# usb2cmi_mini_disp.net
KiCad netlist of a schematic drawn in EAGLE
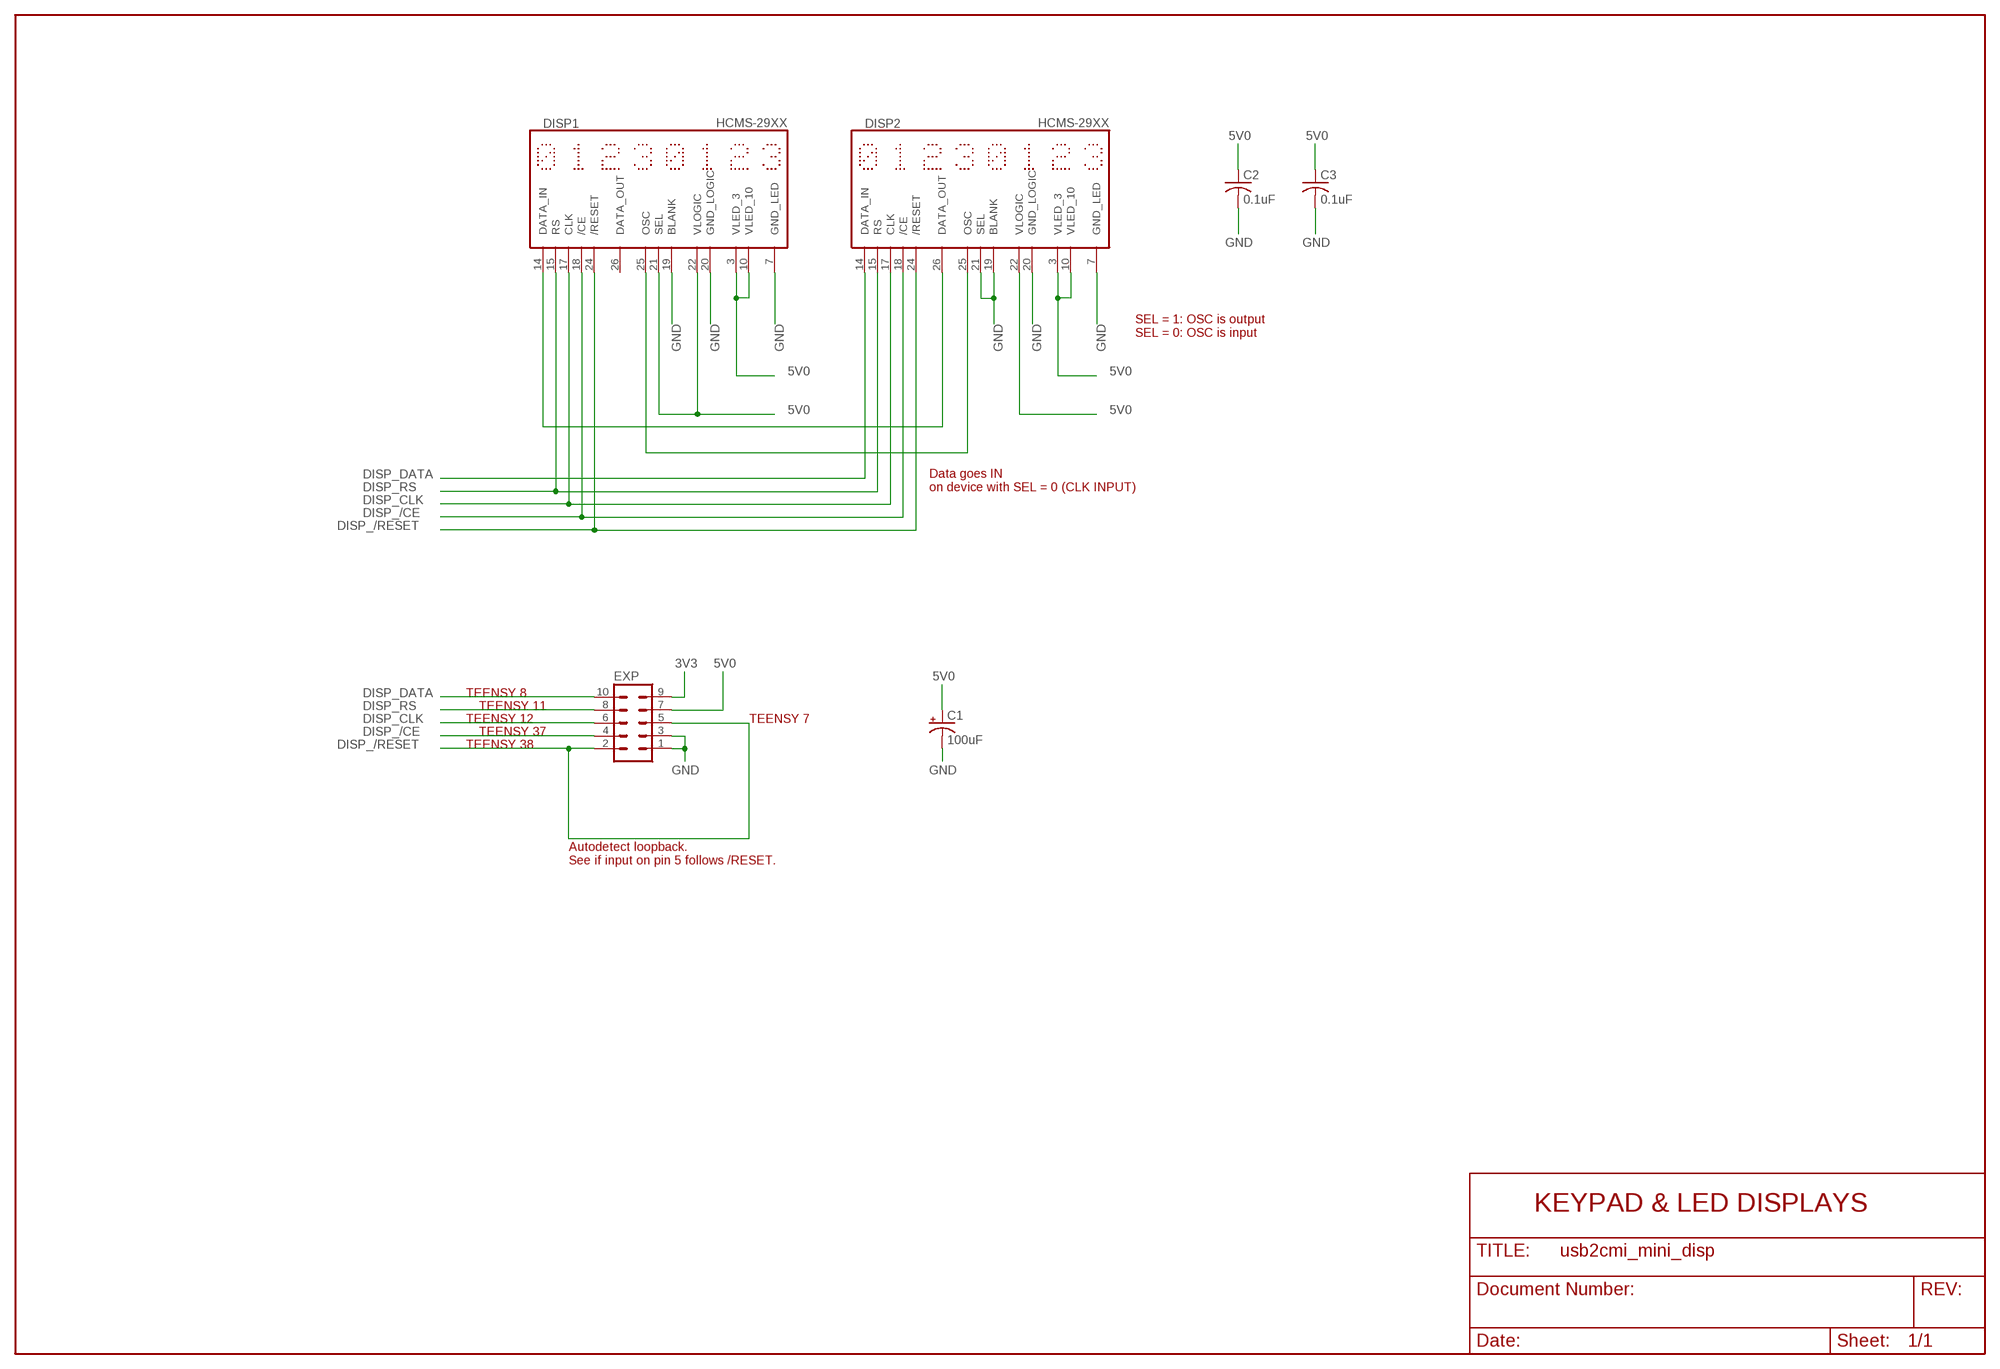
[diagram p0: schematic, sheet 1]

(export (version "E")
  (design (tool "Eeschema 10.0.6"))
  (components
    (comp (ref "C1")
      (value "100uF")
      (footprint "eagle-import:E2,5-7")
      (libsource (lib "eagle-import") (part "CPOL-USE2.5-7"))
    )
    (comp (ref "C2")
      (value "0.1uF")
      (footprint "eagle-import:C050-025X075")
      (libsource (lib "eagle-import") (part "C-US050-025X075"))
    )
    (comp (ref "C3")
      (value "0.1uF")
      (footprint "eagle-import:C050-025X075")
      (libsource (lib "eagle-import") (part "C-US050-025X075"))
    )
    (comp (ref "DISP1")
      (value "HCMS-29XX")
      (footprint "eagle-import:HCMS-29XX")
      (libsource (lib "eagle-import") (part "HCMS-29XX"))
    )
    (comp (ref "DISP2")
      (value "HCMS-29XX")
      (footprint "eagle-import:HCMS-29XX")
      (libsource (lib "eagle-import") (part "HCMS-29XX"))
    )
    (comp (ref "EXP")
      (value "MA05-2")
      (footprint "eagle-import:MA05-2")
      (libsource (lib "eagle-import") (part "MA05-2"))
    )
  )
  (nets
    (net (code "1") (name "/3V3") (class "Default")
      (node (ref "EXP") (pin "9") (pinfunction "9_9") (pintype "passive"))
    )
    (net (code "2") (name "/5V0") (class "Default")
      (node (ref "C1") (pin "+") (pinfunction "+_+") (pintype "passive"))
      (node (ref "C2") (pin "1") (pinfunction "1_1") (pintype "passive"))
      (node (ref "C3") (pin "1") (pinfunction "1_1") (pintype "passive"))
      (node (ref "DISP1") (pin "10") (pinfunction "VLED_10_10") (pintype "bidirectional"))
      (node (ref "DISP1") (pin "21") (pinfunction "SEL_21") (pintype "bidirectional"))
      (node (ref "DISP1") (pin "22") (pinfunction "VLOGIC_22") (pintype "bidirectional"))
      (node (ref "DISP1") (pin "3") (pinfunction "VLED_3_3") (pintype "bidirectional"))
      (node (ref "DISP2") (pin "10") (pinfunction "VLED_10_10") (pintype "bidirectional"))
      (node (ref "DISP2") (pin "22") (pinfunction "VLOGIC_22") (pintype "bidirectional"))
      (node (ref "DISP2") (pin "3") (pinfunction "VLED_3_3") (pintype "bidirectional"))
      (node (ref "EXP") (pin "7") (pinfunction "7_7") (pintype "passive"))
    )
    (net (code "3") (name "/DISP_CLK") (class "Default")
      (node (ref "DISP1") (pin "17") (pinfunction "CLK_17") (pintype "bidirectional"))
      (node (ref "DISP2") (pin "17") (pinfunction "CLK_17") (pintype "bidirectional"))
      (node (ref "EXP") (pin "6") (pinfunction "6_6") (pintype "passive"))
    )
    (net (code "4") (name "/DISP_DATA") (class "Default")
      (node (ref "DISP2") (pin "14") (pinfunction "DATA_IN_14") (pintype "bidirectional"))
      (node (ref "EXP") (pin "10") (pinfunction "10_10") (pintype "passive"))
    )
    (net (code "5") (name "/DISP_RS") (class "Default")
      (node (ref "DISP1") (pin "15") (pinfunction "RS_15") (pintype "bidirectional"))
      (node (ref "DISP2") (pin "15") (pinfunction "RS_15") (pintype "bidirectional"))
      (node (ref "EXP") (pin "8") (pinfunction "8_8") (pintype "passive"))
    )
    (net (code "6") (name "/DISP_{slash}CE") (class "Default")
      (node (ref "DISP1") (pin "18") (pinfunction "/CE_18") (pintype "bidirectional"))
      (node (ref "DISP2") (pin "18") (pinfunction "/CE_18") (pintype "bidirectional"))
      (node (ref "EXP") (pin "4") (pinfunction "4_4") (pintype "passive"))
    )
    (net (code "7") (name "/DISP_{slash}RESET") (class "Default")
      (node (ref "DISP1") (pin "24") (pinfunction "/RESET_24") (pintype "bidirectional"))
      (node (ref "DISP2") (pin "24") (pinfunction "/RESET_24") (pintype "bidirectional"))
      (node (ref "EXP") (pin "2") (pinfunction "2_2") (pintype "passive"))
      (node (ref "EXP") (pin "5") (pinfunction "5_5") (pintype "passive"))
    )
    (net (code "8") (name "/GND") (class "Default")
      (node (ref "C1") (pin "-") (pinfunction "-_-") (pintype "passive"))
      (node (ref "C2") (pin "2") (pinfunction "2_2") (pintype "passive"))
      (node (ref "C3") (pin "2") (pinfunction "2_2") (pintype "passive"))
      (node (ref "DISP1") (pin "19") (pinfunction "BLANK_19") (pintype "bidirectional"))
      (node (ref "DISP1") (pin "20") (pinfunction "GND_LOGIC_20") (pintype "bidirectional"))
      (node (ref "DISP1") (pin "7") (pinfunction "GND_LED_7") (pintype "bidirectional"))
      (node (ref "DISP2") (pin "19") (pinfunction "BLANK_19") (pintype "bidirectional"))
      (node (ref "DISP2") (pin "20") (pinfunction "GND_LOGIC_20") (pintype "bidirectional"))
      (node (ref "DISP2") (pin "21") (pinfunction "SEL_21") (pintype "bidirectional"))
      (node (ref "DISP2") (pin "7") (pinfunction "GND_LED_7") (pintype "bidirectional"))
      (node (ref "EXP") (pin "1") (pinfunction "1_1") (pintype "passive"))
      (node (ref "EXP") (pin "3") (pinfunction "3_3") (pintype "passive"))
    )
    (net (code "9") (name "Net-(DISP1-DATA_IN)") (class "Default")
      (node (ref "DISP1") (pin "14") (pinfunction "DATA_IN_14") (pintype "bidirectional"))
      (node (ref "DISP2") (pin "26") (pinfunction "DATA_OUT_26") (pintype "bidirectional"))
    )
    (net (code "10") (name "Net-(DISP1-OSC)") (class "Default")
      (node (ref "DISP1") (pin "25") (pinfunction "OSC_25") (pintype "bidirectional"))
      (node (ref "DISP2") (pin "25") (pinfunction "OSC_25") (pintype "bidirectional"))
    )
    (net (code "11") (name "unconnected-(DISP1-DATA_OUT-Pad26)") (class "Default")
      (node (ref "DISP1") (pin "26") (pinfunction "DATA_OUT_26") (pintype "bidirectional"))
    )
  )
)
